# Procesador.net
KiCad netlist of a schematic drawn in Altium Designer
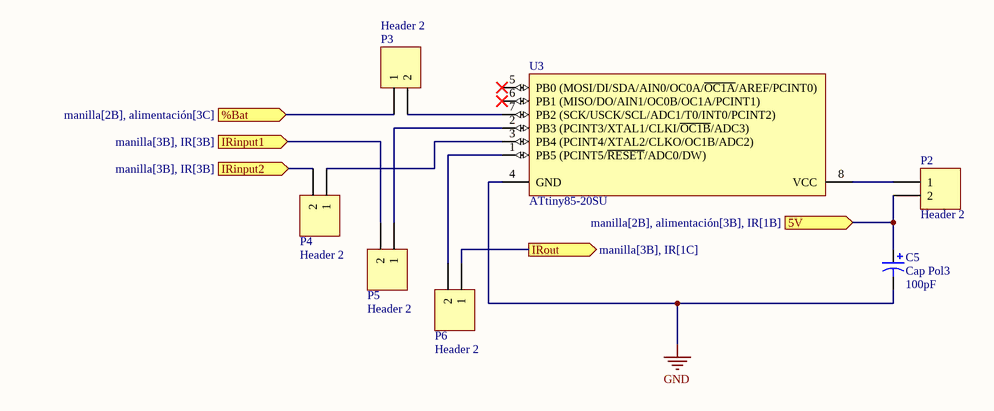
[diagram p0: Procesador.SchDoc]

(export (version "E")
  (design (tool "Eeschema 10.0.6"))
  (components
    (comp (ref "C5")
      (value "Cap Pol3")
      (footprint "C0805")
      (description "Polarized Capacitor (Surface Mount)")
      (fields (field (name "ALTIUM_VALUE") "100pF") (field (name "PUBLISHER") "Altium Limited"))
      (libsource (lib "Miscellaneous Devices") (part "Cap Pol3"))
    )
    (comp (ref "P2")
      (value "Header 2")
      (footprint "HDR1X2")
      (description "Header, 2-Pin")
      (fields (field (name "PUBLISHER") "Altium Limited"))
      (libsource (lib "") (part "Header 2_2"))
    )
    (comp (ref "P3")
      (value "Header 2")
      (footprint "HDR1X2")
      (description "Header, 2-Pin")
      (fields (field (name "PUBLISHER") "Altium Limited"))
      (libsource (lib "") (part "Header 2_1"))
    )
    (comp (ref "P4")
      (value "Header 2")
      (footprint "HDR1X2")
      (description "Header, 2-Pin")
      (fields (field (name "PUBLISHER") "Altium Limited"))
      (libsource (lib "Miscellaneous Connectors") (part "Header 2"))
    )
    (comp (ref "P5")
      (value "Header 2")
      (footprint "HDR1X2")
      (description "Header, 2-Pin")
      (fields (field (name "PUBLISHER") "Altium Limited"))
      (libsource (lib "Miscellaneous Connectors") (part "Header 2"))
    )
    (comp (ref "P6")
      (value "Header 2")
      (footprint "HDR1X2")
      (description "Header, 2-Pin")
      (fields (field (name "PUBLISHER") "Altium Limited"))
      (libsource (lib "Miscellaneous Connectors") (part "Header 2"))
    )
    (comp (ref "U3")
      (value "ATtiny85-20SU")
      (footprint "8S2_M")
      (libsource (lib "Altium Content Vault") (part "MC-8B-ATT25-IL8"))
    )
  )
  (nets
    (net (code "1") (name "/%Bat") (class "Default")
      (node (ref "P3") (pin "1") (pinfunction "1_1") (pintype "passive"))
    )
    (net (code "2") (name "/5V") (class "Default")
      (node (ref "C5") (pin "1") (pinfunction "1_1") (pintype "passive"))
      (node (ref "P2") (pin "2") (pinfunction "2_2") (pintype "passive"))
    )
    (net (code "3") (name "/IRinput1") (class "Default")
      (node (ref "P5") (pin "2") (pinfunction "2_2") (pintype "passive"))
    )
    (net (code "4") (name "/IRinput2") (class "Default")
      (node (ref "P4") (pin "2") (pinfunction "2_2") (pintype "passive"))
    )
    (net (code "5") (name "/IRout") (class "Default")
      (node (ref "P6") (pin "1") (pinfunction "1_1") (pintype "passive"))
    )
    (net (code "6") (name "GND") (class "Default")
      (node (ref "C5") (pin "2") (pinfunction "2_2") (pintype "passive"))
      (node (ref "U3") (pin "4") (pinfunction "GND_4") (pintype "power_in"))
    )
    (net (code "7") (name "Net-(U3-PB2_(SCK{slash}USCK{slash}SCL{slash}ADC1{slash}T0{slash}INT0{slash}PCINT2))") (class "Default")
      (node (ref "P3") (pin "2") (pinfunction "2_2") (pintype "passive"))
      (node (ref "U3") (pin "7") (pinfunction "PB2_(SCK/USCK/SCL/ADC1/T0/INT0/PCINT2)_7") (pintype "bidirectional"))
    )
    (net (code "8") (name "Net-(U3-PB3_(PCINT3{slash}XTAL1{slash}CLKI{slash}~{OC1B}{slash}ADC3))") (class "Default")
      (node (ref "P5") (pin "1") (pinfunction "1_1") (pintype "passive"))
      (node (ref "U3") (pin "2") (pinfunction "PB3_(PCINT3/XTAL1/CLKI/~{OC1B}/ADC3)_2") (pintype "bidirectional"))
    )
    (net (code "9") (name "Net-(U3-PB4_(PCINT4{slash}XTAL2{slash}CLKO{slash}OC1B{slash}ADC2))") (class "Default")
      (node (ref "P4") (pin "1") (pinfunction "1_1") (pintype "passive"))
      (node (ref "U3") (pin "3") (pinfunction "PB4_(PCINT4/XTAL2/CLKO/OC1B/ADC2)_3") (pintype "bidirectional"))
    )
    (net (code "10") (name "Net-(U3-PB5_(PCINT5{slash}~{RESET}{slash}ADC0{slash}DW))") (class "Default")
      (node (ref "P6") (pin "2") (pinfunction "2_2") (pintype "passive"))
      (node (ref "U3") (pin "1") (pinfunction "PB5_(PCINT5/~{RESET}/ADC0/DW)_1") (pintype "bidirectional"))
    )
    (net (code "11") (name "Net-(U3-VCC)") (class "Default")
      (node (ref "P2") (pin "1") (pinfunction "1_1") (pintype "passive"))
      (node (ref "U3") (pin "8") (pinfunction "VCC_8") (pintype "power_in"))
    )
    (net (code "12") (name "unconnected-(U3-PB0_(MOSI{slash}DI{slash}SDA{slash}AIN0{slash}OC0A{slash}~{OC1A}{slash}AREF{slash}PCINT0)-Pad5)") (class "Default")
      (node (ref "U3") (pin "5") (pinfunction "PB0_(MOSI/DI/SDA/AIN0/OC0A/~{OC1A}/AREF/PCINT0)_5") (pintype "bidirectional+no_connect"))
    )
    (net (code "13") (name "unconnected-(U3-PB1_(MISO{slash}DO{slash}AIN1{slash}OC0B{slash}OC1A{slash}PCINT1)-Pad6)") (class "Default")
      (node (ref "U3") (pin "6") (pinfunction "PB1_(MISO/DO/AIN1/OC0B/OC1A/PCINT1)_6") (pintype "bidirectional+no_connect"))
    )
  )
)
